# shieldie-xbee.net
KiCad netlist of a schematic drawn in EAGLE
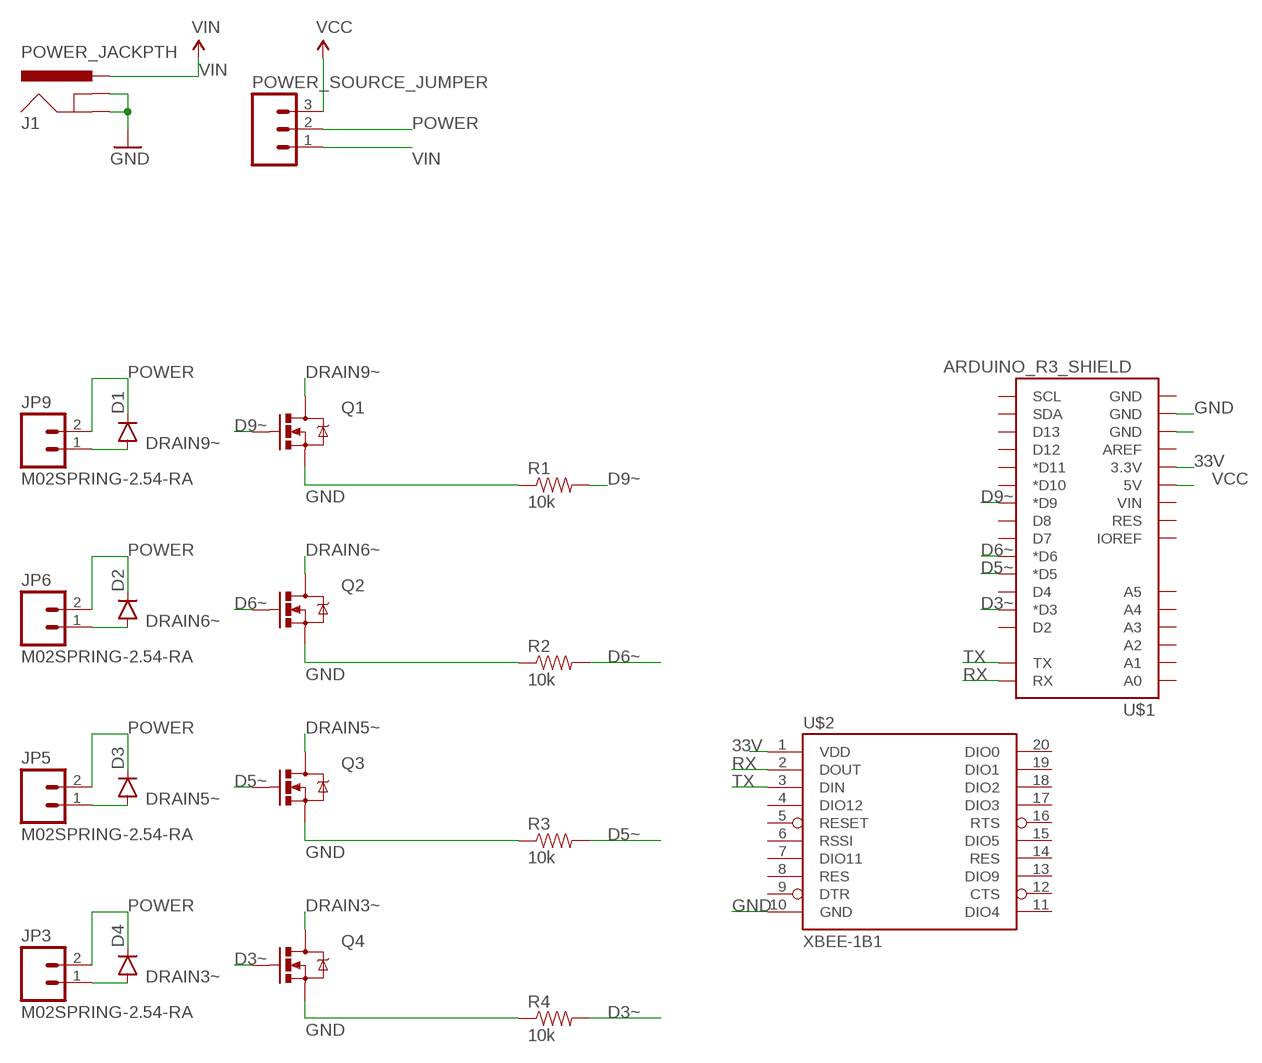
[diagram p0: schematic, sheet 1]

(export (version "E")
  (design (tool "Eeschema 10.0.6"))
  (components
    (comp (ref "D1")
      (value "DIODEPTH")
      (footprint "eagle-import:DIODE-1N4001")
      (libsource (lib "eagle-import") (part "DIODEPTH"))
    )
    (comp (ref "D2")
      (value "DIODEPTH")
      (footprint "eagle-import:DIODE-1N4001")
      (libsource (lib "eagle-import") (part "DIODEPTH"))
    )
    (comp (ref "D3")
      (value "DIODEPTH")
      (footprint "eagle-import:DIODE-1N4001")
      (libsource (lib "eagle-import") (part "DIODEPTH"))
    )
    (comp (ref "D4")
      (value "DIODEPTH")
      (footprint "eagle-import:DIODE-1N4001")
      (libsource (lib "eagle-import") (part "DIODEPTH"))
    )
    (comp (ref "J1")
      (value "POWER_JACKPTH")
      (footprint "eagle-import:POWER_JACK_PTH")
      (libsource (lib "eagle-import") (part "POWER_JACKPTH"))
    )
    (comp (ref "JP3")
      (value "M02SPRING-2.54-RA")
      (footprint "eagle-import:SPRINGTERMINAL-2.54MM-2")
      (libsource (lib "eagle-import") (part "M02SPRING-2.54-RA"))
    )
    (comp (ref "JP5")
      (value "M02SPRING-2.54-RA")
      (footprint "eagle-import:SPRINGTERMINAL-2.54MM-2")
      (libsource (lib "eagle-import") (part "M02SPRING-2.54-RA"))
    )
    (comp (ref "JP6")
      (value "M02SPRING-2.54-RA")
      (footprint "eagle-import:SPRINGTERMINAL-2.54MM-2")
      (libsource (lib "eagle-import") (part "M02SPRING-2.54-RA"))
    )
    (comp (ref "JP9")
      (value "M02SPRING-2.54-RA")
      (footprint "eagle-import:SPRINGTERMINAL-2.54MM-2")
      (libsource (lib "eagle-import") (part "M02SPRING-2.54-RA"))
    )
    (comp (ref "POWER_SOURCE_JUMPER")
      (value "M03JST-PTH-VERT")
      (footprint "eagle-import:JST-3-PTH-VERT")
      (libsource (lib "eagle-import") (part "M03JST-PTH-VERT"))
    )
    (comp (ref "Q1")
      (value "MOSFET-NCHANNELFQP30N06L")
      (footprint "eagle-import:TO220V")
      (libsource (lib "eagle-import") (part "MOSFET-NCHANNELFQP30N06L"))
    )
    (comp (ref "Q2")
      (value "MOSFET-NCHANNELFQP30N06L")
      (footprint "eagle-import:TO220V")
      (libsource (lib "eagle-import") (part "MOSFET-NCHANNELFQP30N06L"))
    )
    (comp (ref "Q3")
      (value "MOSFET-NCHANNELFQP30N06L")
      (footprint "eagle-import:TO220V")
      (libsource (lib "eagle-import") (part "MOSFET-NCHANNELFQP30N06L"))
    )
    (comp (ref "Q4")
      (value "MOSFET-NCHANNELFQP30N06L")
      (footprint "eagle-import:TO220V")
      (libsource (lib "eagle-import") (part "MOSFET-NCHANNELFQP30N06L"))
    )
    (comp (ref "R1")
      (value "10k")
      (footprint "eagle-import:AXIAL-0.3")
      (libsource (lib "eagle-import") (part "10KOHM-1/4W5%(PTH)"))
    )
    (comp (ref "R2")
      (value "10k")
      (footprint "eagle-import:AXIAL-0.3")
      (libsource (lib "eagle-import") (part "10KOHM-1/4W5%(PTH)"))
    )
    (comp (ref "R3")
      (value "10k")
      (footprint "eagle-import:AXIAL-0.3")
      (libsource (lib "eagle-import") (part "10KOHM-1/4W5%(PTH)"))
    )
    (comp (ref "R4")
      (value "10k")
      (footprint "eagle-import:AXIAL-0.3")
      (libsource (lib "eagle-import") (part "10KOHM-1/4W5%(PTH)"))
    )
    (comp (ref "U$1")
      (value "ARDUINO_R3_SHIELD")
      (footprint "eagle-import:UNO_R3_SHIELD")
      (libsource (lib "eagle-import") (part "ARDUINO_R3_SHIELD"))
    )
    (comp (ref "U$2")
      (value "XBEE-1B1")
      (footprint "eagle-import:XBEE-1")
      (libsource (lib "eagle-import") (part "XBEE-1B1"))
    )
  )
  (nets
    (net (code "1") (name "/33V") (class "Default")
      (node (ref "U$1") (pin "3.3V") (pinfunction "3.3V_3.3V") (pintype "bidirectional"))
      (node (ref "U$2") (pin "1") (pinfunction "VDD_1") (pintype "power_in"))
    )
    (net (code "2") (name "/D3~{}") (class "Default")
      (node (ref "Q4") (pin "1") (pinfunction "G_1") (pintype "passive"))
      (node (ref "R4") (pin "P$2") (pinfunction "2_P$2") (pintype "passive"))
      (node (ref "U$1") (pin "D3") (pinfunction "*D3_D3") (pintype "bidirectional"))
    )
    (net (code "3") (name "/D5~{}") (class "Default")
      (node (ref "Q3") (pin "1") (pinfunction "G_1") (pintype "passive"))
      (node (ref "R3") (pin "P$2") (pinfunction "2_P$2") (pintype "passive"))
      (node (ref "U$1") (pin "D5") (pinfunction "*D5_D5") (pintype "bidirectional"))
    )
    (net (code "4") (name "/D6~{}") (class "Default")
      (node (ref "Q2") (pin "1") (pinfunction "G_1") (pintype "passive"))
      (node (ref "R2") (pin "P$2") (pinfunction "2_P$2") (pintype "passive"))
      (node (ref "U$1") (pin "D6") (pinfunction "*D6_D6") (pintype "bidirectional"))
    )
    (net (code "5") (name "/D9~{}") (class "Default")
      (node (ref "Q1") (pin "1") (pinfunction "G_1") (pintype "passive"))
      (node (ref "R1") (pin "P$2") (pinfunction "2_P$2") (pintype "passive"))
      (node (ref "U$1") (pin "D9") (pinfunction "*D9_D9") (pintype "bidirectional"))
    )
    (net (code "6") (name "/DRAIN3~{}") (class "Default")
      (node (ref "D4") (pin "A") (pinfunction "A_A") (pintype "passive"))
      (node (ref "JP3") (pin "1") (pinfunction "1_1") (pintype "passive"))
      (node (ref "Q4") (pin "2") (pinfunction "D_2") (pintype "passive"))
    )
    (net (code "7") (name "/DRAIN5~{}") (class "Default")
      (node (ref "D3") (pin "A") (pinfunction "A_A") (pintype "passive"))
      (node (ref "JP5") (pin "1") (pinfunction "1_1") (pintype "passive"))
      (node (ref "Q3") (pin "2") (pinfunction "D_2") (pintype "passive"))
    )
    (net (code "8") (name "/DRAIN6~{}") (class "Default")
      (node (ref "D2") (pin "A") (pinfunction "A_A") (pintype "passive"))
      (node (ref "JP6") (pin "1") (pinfunction "1_1") (pintype "passive"))
      (node (ref "Q2") (pin "2") (pinfunction "D_2") (pintype "passive"))
    )
    (net (code "9") (name "/DRAIN9~{}") (class "Default")
      (node (ref "D1") (pin "A") (pinfunction "A_A") (pintype "passive"))
      (node (ref "JP9") (pin "1") (pinfunction "1_1") (pintype "passive"))
      (node (ref "Q1") (pin "2") (pinfunction "D_2") (pintype "passive"))
    )
    (net (code "10") (name "/POWER") (class "Default")
      (node (ref "D1") (pin "C") (pinfunction "C_C") (pintype "passive"))
      (node (ref "D2") (pin "C") (pinfunction "C_C") (pintype "passive"))
      (node (ref "D3") (pin "C") (pinfunction "C_C") (pintype "passive"))
      (node (ref "D4") (pin "C") (pinfunction "C_C") (pintype "passive"))
      (node (ref "JP3") (pin "2") (pinfunction "2_2") (pintype "passive"))
      (node (ref "JP5") (pin "2") (pinfunction "2_2") (pintype "passive"))
      (node (ref "JP6") (pin "2") (pinfunction "2_2") (pintype "passive"))
      (node (ref "JP9") (pin "2") (pinfunction "2_2") (pintype "passive"))
      (node (ref "POWER_SOURCE_JUMPER") (pin "2") (pinfunction "2_2") (pintype "passive"))
    )
    (net (code "11") (name "/RX") (class "Default")
      (node (ref "U$1") (pin "RX") (pinfunction "RX_RX") (pintype "bidirectional"))
      (node (ref "U$2") (pin "2") (pinfunction "DOUT_2") (pintype "output"))
    )
    (net (code "12") (name "/TX") (class "Default")
      (node (ref "U$1") (pin "TX") (pinfunction "TX_TX") (pintype "bidirectional"))
      (node (ref "U$2") (pin "3") (pinfunction "DIN_3") (pintype "input"))
    )
    (net (code "13") (name "GND") (class "Default")
      (node (ref "J1") (pin "GND") (pinfunction "GND_GND") (pintype "bidirectional"))
      (node (ref "J1") (pin "GNDBREAK") (pinfunction "GNDBREAK_GNDBREAK") (pintype "bidirectional"))
      (node (ref "Q1") (pin "3") (pinfunction "S_3") (pintype "passive"))
      (node (ref "Q2") (pin "3") (pinfunction "S_3") (pintype "passive"))
      (node (ref "Q3") (pin "3") (pinfunction "S_3") (pintype "passive"))
      (node (ref "Q4") (pin "3") (pinfunction "S_3") (pintype "passive"))
      (node (ref "R1") (pin "P$1") (pinfunction "1_P$1") (pintype "passive"))
      (node (ref "R2") (pin "P$1") (pinfunction "1_P$1") (pintype "passive"))
      (node (ref "R3") (pin "P$1") (pinfunction "1_P$1") (pintype "passive"))
      (node (ref "R4") (pin "P$1") (pinfunction "1_P$1") (pintype "passive"))
      (node (ref "U$1") (pin "GND@1") (pinfunction "GND_GND@1") (pintype "bidirectional"))
      (node (ref "U$1") (pin "GND@2") (pinfunction "GND_GND@2") (pintype "bidirectional"))
      (node (ref "U$2") (pin "10") (pinfunction "GND_10") (pintype "power_in"))
    )
    (net (code "14") (name "VCC") (class "Default")
      (node (ref "POWER_SOURCE_JUMPER") (pin "3") (pinfunction "3_3") (pintype "passive"))
      (node (ref "U$1") (pin "5V") (pinfunction "5V_5V") (pintype "bidirectional"))
    )
    (net (code "15") (name "VIN") (class "Default")
      (node (ref "J1") (pin "PWR") (pinfunction "PWR_PWR") (pintype "bidirectional"))
      (node (ref "POWER_SOURCE_JUMPER") (pin "1") (pinfunction "1_1") (pintype "passive"))
    )
    (net (code "16") (name "unconnected-(U$1-*D10-PadD10)") (class "Default")
      (node (ref "U$1") (pin "D10") (pinfunction "*D10_D10") (pintype "bidirectional"))
    )
    (net (code "17") (name "unconnected-(U$1-*D11-PadD11)") (class "Default")
      (node (ref "U$1") (pin "D11") (pinfunction "*D11_D11") (pintype "bidirectional"))
    )
    (net (code "18") (name "unconnected-(U$1-GND-PadGND@0)") (class "Default")
      (node (ref "U$1") (pin "GND@0") (pinfunction "GND_GND@0") (pintype "bidirectional"))
    )
    (net (code "19") (name "unconnected-(U$1-PadA0)") (class "Default")
      (node (ref "U$1") (pin "A0") (pinfunction "A0_A0") (pintype "bidirectional"))
    )
    (net (code "20") (name "unconnected-(U$1-PadA1)") (class "Default")
      (node (ref "U$1") (pin "A1") (pinfunction "A1_A1") (pintype "bidirectional"))
    )
    (net (code "21") (name "unconnected-(U$1-PadA2)") (class "Default")
      (node (ref "U$1") (pin "A2") (pinfunction "A2_A2") (pintype "bidirectional"))
    )
    (net (code "22") (name "unconnected-(U$1-PadA3)") (class "Default")
      (node (ref "U$1") (pin "A3") (pinfunction "A3_A3") (pintype "bidirectional"))
    )
    (net (code "23") (name "unconnected-(U$1-PadA4)") (class "Default")
      (node (ref "U$1") (pin "A4") (pinfunction "A4_A4") (pintype "bidirectional"))
    )
    (net (code "24") (name "unconnected-(U$1-PadA5)") (class "Default")
      (node (ref "U$1") (pin "A5") (pinfunction "A5_A5") (pintype "bidirectional"))
    )
    (net (code "25") (name "unconnected-(U$1-PadAREF)") (class "Default")
      (node (ref "U$1") (pin "AREF") (pinfunction "AREF_AREF") (pintype "bidirectional"))
    )
    (net (code "26") (name "unconnected-(U$1-PadD2)") (class "Default")
      (node (ref "U$1") (pin "D2") (pinfunction "D2_D2") (pintype "bidirectional"))
    )
    (net (code "27") (name "unconnected-(U$1-PadD4)") (class "Default")
      (node (ref "U$1") (pin "D4") (pinfunction "D4_D4") (pintype "bidirectional"))
    )
    (net (code "28") (name "unconnected-(U$1-PadD7)") (class "Default")
      (node (ref "U$1") (pin "D7") (pinfunction "D7_D7") (pintype "bidirectional"))
    )
    (net (code "29") (name "unconnected-(U$1-PadD8)") (class "Default")
      (node (ref "U$1") (pin "D8") (pinfunction "D8_D8") (pintype "bidirectional"))
    )
    (net (code "30") (name "unconnected-(U$1-PadD12)") (class "Default")
      (node (ref "U$1") (pin "D12") (pinfunction "D12_D12") (pintype "bidirectional"))
    )
    (net (code "31") (name "unconnected-(U$1-PadD13)") (class "Default")
      (node (ref "U$1") (pin "D13") (pinfunction "D13_D13") (pintype "bidirectional"))
    )
    (net (code "32") (name "unconnected-(U$1-PadIOREF)") (class "Default")
      (node (ref "U$1") (pin "IOREF") (pinfunction "IOREF_IOREF") (pintype "bidirectional"))
    )
    (net (code "33") (name "unconnected-(U$1-PadRES)") (class "Default")
      (node (ref "U$1") (pin "RES") (pinfunction "RES_RES") (pintype "bidirectional"))
    )
    (net (code "34") (name "unconnected-(U$1-PadSCL)") (class "Default")
      (node (ref "U$1") (pin "SCL") (pinfunction "SCL_SCL") (pintype "bidirectional"))
    )
    (net (code "35") (name "unconnected-(U$1-PadSDA)") (class "Default")
      (node (ref "U$1") (pin "SDA") (pinfunction "SDA_SDA") (pintype "bidirectional"))
    )
    (net (code "36") (name "unconnected-(U$1-PadVIN)") (class "Default")
      (node (ref "U$1") (pin "VIN") (pinfunction "VIN_VIN") (pintype "bidirectional"))
    )
    (net (code "37") (name "unconnected-(U$2-CTS-Pad12)") (class "Default")
      (node (ref "U$2") (pin "12") (pinfunction "CTS_12") (pintype "output"))
    )
    (net (code "38") (name "unconnected-(U$2-DIO0-Pad20)") (class "Default")
      (node (ref "U$2") (pin "20") (pinfunction "DIO0_20") (pintype "bidirectional"))
    )
    (net (code "39") (name "unconnected-(U$2-DIO1-Pad19)") (class "Default")
      (node (ref "U$2") (pin "19") (pinfunction "DIO1_19") (pintype "bidirectional"))
    )
    (net (code "40") (name "unconnected-(U$2-DIO2-Pad18)") (class "Default")
      (node (ref "U$2") (pin "18") (pinfunction "DIO2_18") (pintype "bidirectional"))
    )
    (net (code "41") (name "unconnected-(U$2-DIO3-Pad17)") (class "Default")
      (node (ref "U$2") (pin "17") (pinfunction "DIO3_17") (pintype "bidirectional"))
    )
    (net (code "42") (name "unconnected-(U$2-DIO4-Pad11)") (class "Default")
      (node (ref "U$2") (pin "11") (pinfunction "DIO4_11") (pintype "bidirectional"))
    )
    (net (code "43") (name "unconnected-(U$2-DIO5-Pad15)") (class "Default")
      (node (ref "U$2") (pin "15") (pinfunction "DIO5_15") (pintype "bidirectional"))
    )
    (net (code "44") (name "unconnected-(U$2-DIO9-Pad13)") (class "Default")
      (node (ref "U$2") (pin "13") (pinfunction "DIO9_13") (pintype "bidirectional"))
    )
    (net (code "45") (name "unconnected-(U$2-DIO11-Pad7)") (class "Default")
      (node (ref "U$2") (pin "7") (pinfunction "DIO11_7") (pintype "bidirectional"))
    )
    (net (code "46") (name "unconnected-(U$2-DIO12-Pad4)") (class "Default")
      (node (ref "U$2") (pin "4") (pinfunction "DIO12_4") (pintype "bidirectional"))
    )
    (net (code "47") (name "unconnected-(U$2-DTR-Pad9)") (class "Default")
      (node (ref "U$2") (pin "9") (pinfunction "DTR_9") (pintype "bidirectional"))
    )
    (net (code "48") (name "unconnected-(U$2-RES-Pad8)") (class "Default")
      (node (ref "U$2") (pin "8") (pinfunction "RES_8") (pintype "bidirectional"))
    )
    (net (code "49") (name "unconnected-(U$2-RES-Pad14)") (class "Default")
      (node (ref "U$2") (pin "14") (pinfunction "RES_14") (pintype "bidirectional"))
    )
    (net (code "50") (name "unconnected-(U$2-RESET-Pad5)") (class "Default")
      (node (ref "U$2") (pin "5") (pinfunction "RESET_5") (pintype "input"))
    )
    (net (code "51") (name "unconnected-(U$2-RSSI-Pad6)") (class "Default")
      (node (ref "U$2") (pin "6") (pinfunction "RSSI_6") (pintype "bidirectional"))
    )
    (net (code "52") (name "unconnected-(U$2-RTS-Pad16)") (class "Default")
      (node (ref "U$2") (pin "16") (pinfunction "RTS_16") (pintype "input"))
    )
  )
)
